# Sheet1.net
KiCad netlist of a schematic drawn in Altium Designer
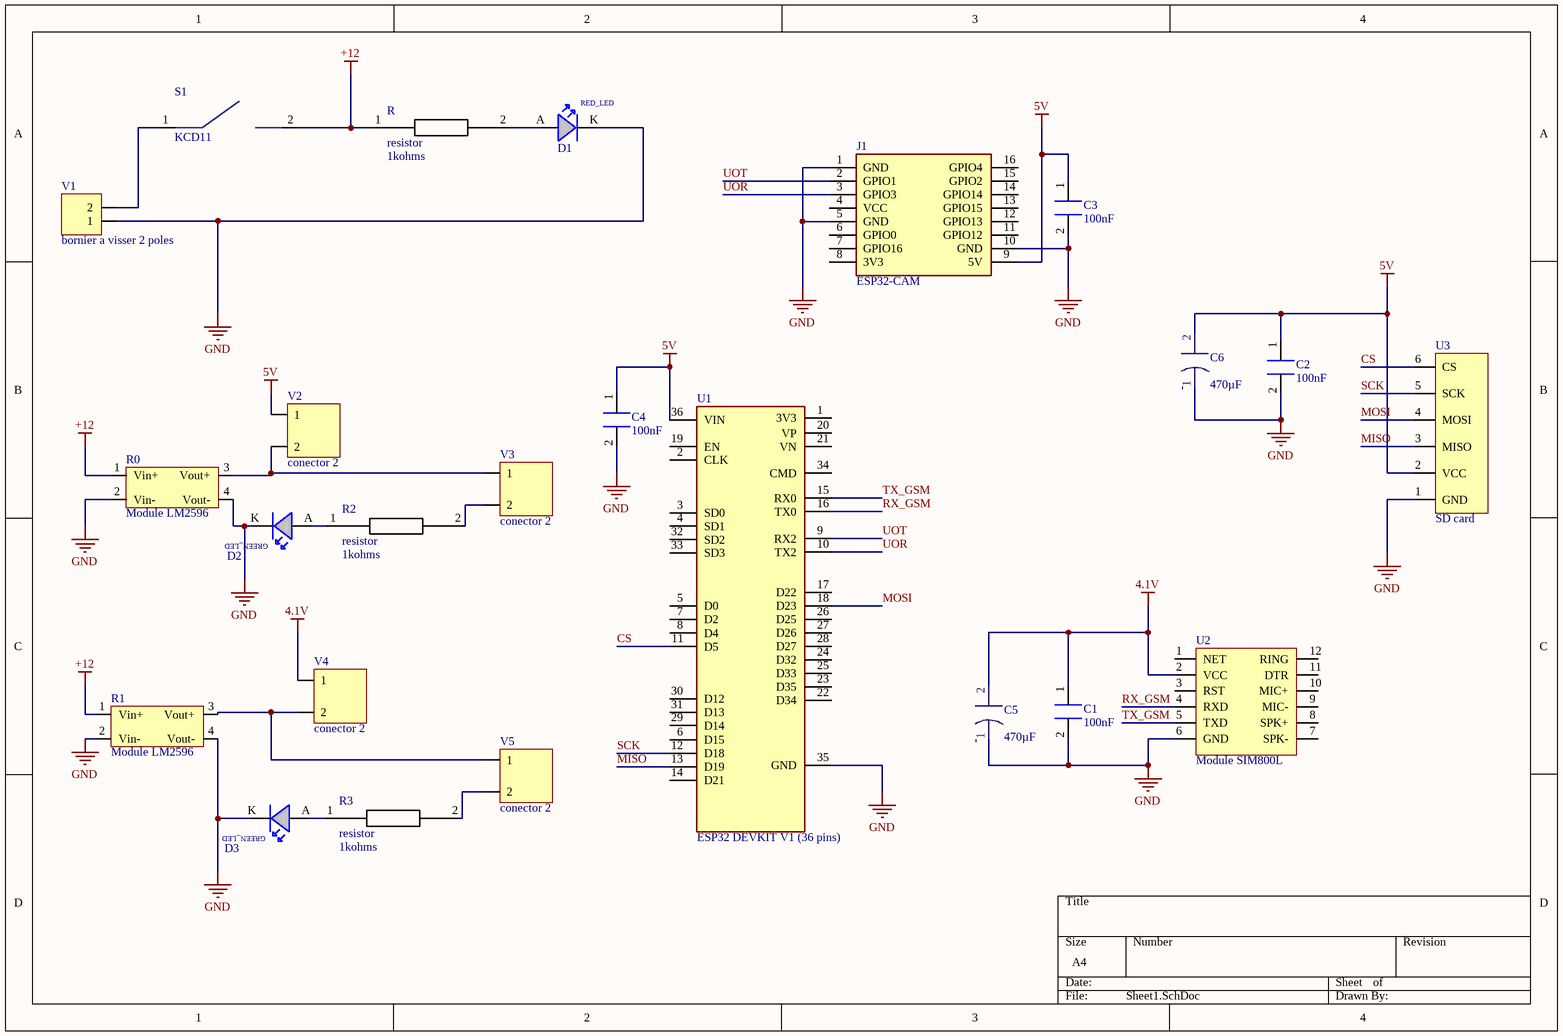
[diagram p0: Sheet1.SchDoc]

(export (version "E")
  (design (tool "Eeschema 10.0.6"))
  (components
    (comp (ref "C1")
      (value "capacitor")
      (footprint "CAPACITOR")
      (fields (field (name "CAP EN UF OU NF") "100nF"))
      (libsource (lib "Devices") (part "capacitor"))
    )
    (comp (ref "C2")
      (value "capacitor")
      (footprint "CAPACITOR")
      (fields (field (name "CAP EN UF OU NF") "100nF"))
      (libsource (lib "Devices") (part "capacitor"))
    )
    (comp (ref "C3")
      (value "capacitor")
      (footprint "CAPACITOR")
      (fields (field (name "CAP EN UF OU NF") "100nF"))
      (libsource (lib "Devices") (part "capacitor"))
    )
    (comp (ref "C4")
      (value "capacitor")
      (footprint "CAPACITOR")
      (fields (field (name "CAP EN UF OU NF") "100nF"))
      (libsource (lib "Devices") (part "capacitor"))
    )
    (comp (ref "C5")
      (value "470µF")
      (footprint "condensateur chimique 470f 16v -")
      (fields (field (name "Comment") "condensateur chimique_470uF"))
      (libsource (lib "condensateur") (part "condensateur chimique_470uF"))
    )
    (comp (ref "C6")
      (value "470µF")
      (footprint "condensateur chimique 470f 16v -")
      (fields (field (name "Comment") "condensateur chimique_470uF"))
      (libsource (lib "condensateur") (part "condensateur chimique_470uF"))
    )
    (comp (ref "D1") (value "LED_RED") (footprint "LED") (libsource (lib "Devices") (part "LED_RED")))
    (comp (ref "D2")
      (value "LED_GREEN")
      (footprint "LED_GREEN")
      (libsource (lib "Devices") (part "LED_GREEN"))
    )
    (comp (ref "D3")
      (value "LED_GREEN")
      (footprint "LED_GREEN")
      (libsource (lib "Devices") (part "LED_GREEN"))
    )
    (comp (ref "J1")
      (value "ESP32-CAM")
      (footprint "ESP32-CAM")
      (fields (field (name "MF") "AI-Thinker"))
      (libsource (lib "esp32") (part "ESP32-CAM"))
    )
    (comp (ref "R")
      (value "resistor")
      (footprint "RESISTOR")
      (fields (field (name "R") "1kohms"))
      (libsource (lib "resistor") (part "resistor"))
    )
    (comp (ref "R0")
      (value "Module LM2596")
      (footprint "Module LM2596")
      (libsource (lib "Alimentation Réglable") (part "Module LM2596"))
    )
    (comp (ref "R1")
      (value "Module LM2596")
      (footprint "Module LM2596")
      (libsource (lib "Alimentation Réglable") (part "Module LM2596"))
    )
    (comp (ref "R2")
      (value "resistor")
      (footprint "RESISTOR")
      (fields (field (name "R") "1kohms"))
      (libsource (lib "resistor") (part "resistor"))
    )
    (comp (ref "R3")
      (value "resistor")
      (footprint "RESISTOR")
      (fields (field (name "R") "1kohms"))
      (libsource (lib "resistor") (part "resistor"))
    )
    (comp (ref "S1") (value "KCD11") (footprint "PCBComponent_1") (libsource (lib "switch") (part "KCD11")))
    (comp (ref "U1")
      (value "ESP32 DEVKIT V1 (36 pins)")
      (footprint "ESP32 DEVKIT V1 (36 pins)")
      (fields (field (name "MF") "Do it") (field (name "MP") "ESP32-DEVKIT-V1"))
      (libsource (lib "esp32") (part "ESP32 DEVKIT V1 (36 pins)"))
    )
    (comp (ref "U2")
      (value "Module SIM800L")
      (footprint "SIM800L")
      (libsource (lib "SIM800L") (part "SIM800L"))
    )
    (comp (ref "U3")
      (value "SD card")
      (footprint "SULLINS_PPTC061LFBN-RC - duplicate")
      (libsource (lib "SD card") (part "SD card V2"))
    )
    (comp (ref "V1")
      (value "bornier a visser 2 poles")
      (footprint "bornier a visser 2 poles")
      (libsource (lib "bornier") (part "bornier a visser 2 poles"))
    )
    (comp (ref "V2")
      (value "conector 2")
      (footprint "PCBComponent_1")
      (libsource (lib "connector devives") (part "conector 2"))
    )
    (comp (ref "V3")
      (value "conector 2")
      (footprint "PCBComponent_1")
      (libsource (lib "connector devives") (part "conector 2"))
    )
    (comp (ref "V4")
      (value "conector 2")
      (footprint "PCBComponent_1")
      (libsource (lib "connector devives") (part "conector 2"))
    )
    (comp (ref "V5")
      (value "conector 2")
      (footprint "PCBComponent_1")
      (libsource (lib "connector devives") (part "conector 2"))
    )
  )
  (nets
    (net (code "1") (name "+12") (class "Default")
      (node (ref "R") (pin "1") (pinfunction "1_1") (pintype "passive"))
      (node (ref "R0") (pin "1") (pinfunction "Vin+_1") (pintype "passive"))
      (node (ref "R1") (pin "1") (pinfunction "Vin+_1") (pintype "passive"))
      (node (ref "S1") (pin "2") (pinfunction "2_2") (pintype "passive"))
    )
    (net (code "2") (name "/CS") (class "Default")
      (node (ref "U1") (pin "11") (pinfunction "D5_11") (pintype "passive"))
      (node (ref "U3") (pin "6") (pinfunction "CS_6") (pintype "passive"))
    )
    (net (code "3") (name "/MISO") (class "Default")
      (node (ref "U1") (pin "13") (pinfunction "D19_13") (pintype "passive"))
      (node (ref "U3") (pin "3") (pinfunction "MISO_3") (pintype "passive"))
    )
    (net (code "4") (name "/MOSI") (class "Default")
      (node (ref "U1") (pin "18") (pinfunction "D23_18") (pintype "passive"))
      (node (ref "U3") (pin "4") (pinfunction "MOSI_4") (pintype "passive"))
    )
    (net (code "5") (name "/RX_GSM") (class "Default")
      (node (ref "U1") (pin "16") (pinfunction "TX0_16") (pintype "passive"))
      (node (ref "U2") (pin "4") (pinfunction "RXD_4") (pintype "passive"))
    )
    (net (code "6") (name "/SCK") (class "Default")
      (node (ref "U1") (pin "12") (pinfunction "D18_12") (pintype "passive"))
      (node (ref "U3") (pin "5") (pinfunction "SCK_5") (pintype "passive"))
    )
    (net (code "7") (name "/TX_GSM") (class "Default")
      (node (ref "U1") (pin "15") (pinfunction "RX0_15") (pintype "passive"))
      (node (ref "U2") (pin "5") (pinfunction "TXD_5") (pintype "passive"))
    )
    (net (code "8") (name "/UOR") (class "Default")
      (node (ref "J1") (pin "3") (pinfunction "GPIO3_3") (pintype "passive"))
      (node (ref "U1") (pin "10") (pinfunction "TX2_10") (pintype "passive"))
    )
    (net (code "9") (name "/UOT") (class "Default")
      (node (ref "J1") (pin "2") (pinfunction "GPIO1_2") (pintype "passive"))
      (node (ref "U1") (pin "9") (pinfunction "RX2_9") (pintype "passive"))
    )
    (net (code "10") (name "4.1V") (class "Default")
      (node (ref "C1") (pin "1") (pinfunction "1_1") (pintype "passive"))
      (node (ref "C5") (pin "2") (pinfunction "2_2") (pintype "passive"))
      (node (ref "U2") (pin "2") (pinfunction "VCC_2") (pintype "passive"))
      (node (ref "V4") (pin "1") (pinfunction "1_1") (pintype "passive"))
    )
    (net (code "11") (name "5V") (class "Default")
      (node (ref "C2") (pin "1") (pinfunction "1_1") (pintype "passive"))
      (node (ref "C3") (pin "1") (pinfunction "1_1") (pintype "passive"))
      (node (ref "C4") (pin "1") (pinfunction "1_1") (pintype "passive"))
      (node (ref "C6") (pin "2") (pinfunction "2_2") (pintype "passive"))
      (node (ref "J1") (pin "9") (pinfunction "5V_9") (pintype "passive"))
      (node (ref "U1") (pin "36") (pinfunction "VIN_36") (pintype "passive"))
      (node (ref "U3") (pin "2") (pinfunction "VCC_2") (pintype "passive"))
      (node (ref "V2") (pin "1") (pinfunction "1_1") (pintype "passive"))
    )
    (net (code "12") (name "GND") (class "Default")
      (node (ref "C1") (pin "2") (pinfunction "2_2") (pintype "passive"))
      (node (ref "C2") (pin "2") (pinfunction "2_2") (pintype "passive"))
      (node (ref "C3") (pin "2") (pinfunction "2_2") (pintype "passive"))
      (node (ref "C4") (pin "2") (pinfunction "2_2") (pintype "passive"))
      (node (ref "C5") (pin "1") (pinfunction "1_1") (pintype "passive"))
      (node (ref "C6") (pin "1") (pinfunction "1_1") (pintype "passive"))
      (node (ref "D1") (pin "K") (pintype "passive"))
      (node (ref "D2") (pin "K") (pintype "passive"))
      (node (ref "D3") (pin "K") (pintype "passive"))
      (node (ref "J1") (pin "1") (pinfunction "GND_1") (pintype "passive"))
      (node (ref "J1") (pin "10") (pinfunction "GND_10") (pintype "passive"))
      (node (ref "J1") (pin "5") (pinfunction "GND_5") (pintype "passive"))
      (node (ref "R0") (pin "2") (pinfunction "Vin-_2") (pintype "passive"))
      (node (ref "R0") (pin "4") (pinfunction "Vout-_4") (pintype "passive"))
      (node (ref "R1") (pin "2") (pinfunction "Vin-_2") (pintype "passive"))
      (node (ref "R1") (pin "4") (pinfunction "Vout-_4") (pintype "passive"))
      (node (ref "U1") (pin "35") (pinfunction "GND_35") (pintype "passive"))
      (node (ref "U2") (pin "6") (pinfunction "GND_6") (pintype "passive"))
      (node (ref "U3") (pin "1") (pinfunction "GND_1") (pintype "passive"))
      (node (ref "V1") (pin "1") (pinfunction "1_1") (pintype "passive"))
    )
    (net (code "13") (name "Net-(D1-PadA)") (class "Default")
      (node (ref "D1") (pin "A") (pintype "passive"))
      (node (ref "R") (pin "2") (pinfunction "2_2") (pintype "passive"))
    )
    (net (code "14") (name "Net-(D2-PadA)") (class "Default")
      (node (ref "D2") (pin "A") (pintype "passive"))
      (node (ref "R2") (pin "1") (pinfunction "1_1") (pintype "passive"))
    )
    (net (code "15") (name "Net-(D3-PadA)") (class "Default")
      (node (ref "D3") (pin "A") (pintype "passive"))
      (node (ref "R3") (pin "1") (pinfunction "1_1") (pintype "passive"))
    )
    (net (code "16") (name "Net-(R0-Vout+)") (class "Default")
      (node (ref "R0") (pin "3") (pinfunction "Vout+_3") (pintype "passive"))
      (node (ref "V2") (pin "2") (pinfunction "2_2") (pintype "passive"))
      (node (ref "V3") (pin "1") (pinfunction "1_1") (pintype "passive"))
    )
    (net (code "17") (name "Net-(R1-Vout+)") (class "Default")
      (node (ref "R1") (pin "3") (pinfunction "Vout+_3") (pintype "passive"))
      (node (ref "V4") (pin "2") (pinfunction "2_2") (pintype "passive"))
      (node (ref "V5") (pin "1") (pinfunction "1_1") (pintype "passive"))
    )
    (net (code "18") (name "Net-(R2-Pad2)") (class "Default")
      (node (ref "R2") (pin "2") (pinfunction "2_2") (pintype "passive"))
      (node (ref "V3") (pin "2") (pinfunction "2_2") (pintype "passive"))
    )
    (net (code "19") (name "Net-(R3-Pad2)") (class "Default")
      (node (ref "R3") (pin "2") (pinfunction "2_2") (pintype "passive"))
      (node (ref "V5") (pin "2") (pinfunction "2_2") (pintype "passive"))
    )
    (net (code "20") (name "Net-(S1-Pad1)") (class "Default")
      (node (ref "S1") (pin "1") (pinfunction "1_1") (pintype "passive"))
      (node (ref "V1") (pin "2") (pinfunction "2_2") (pintype "passive"))
    )
    (net (code "21") (name "unconnected-(J1-3V3-Pad8)") (class "Default")
      (node (ref "J1") (pin "8") (pinfunction "3V3_8") (pintype "passive"))
    )
    (net (code "22") (name "unconnected-(J1-GPIO0-Pad6)") (class "Default")
      (node (ref "J1") (pin "6") (pinfunction "GPIO0_6") (pintype "passive"))
    )
    (net (code "23") (name "unconnected-(J1-GPIO2-Pad15)") (class "Default")
      (node (ref "J1") (pin "15") (pinfunction "GPIO2_15") (pintype "passive"))
    )
    (net (code "24") (name "unconnected-(J1-GPIO4-Pad16)") (class "Default")
      (node (ref "J1") (pin "16") (pinfunction "GPIO4_16") (pintype "passive"))
    )
    (net (code "25") (name "unconnected-(J1-GPIO12-Pad11)") (class "Default")
      (node (ref "J1") (pin "11") (pinfunction "GPIO12_11") (pintype "passive"))
    )
    (net (code "26") (name "unconnected-(J1-GPIO13-Pad12)") (class "Default")
      (node (ref "J1") (pin "12") (pinfunction "GPIO13_12") (pintype "passive"))
    )
    (net (code "27") (name "unconnected-(J1-GPIO14-Pad14)") (class "Default")
      (node (ref "J1") (pin "14") (pinfunction "GPIO14_14") (pintype "passive"))
    )
    (net (code "28") (name "unconnected-(J1-GPIO15-Pad13)") (class "Default")
      (node (ref "J1") (pin "13") (pinfunction "GPIO15_13") (pintype "passive"))
    )
    (net (code "29") (name "unconnected-(J1-GPIO16-Pad7)") (class "Default")
      (node (ref "J1") (pin "7") (pinfunction "GPIO16_7") (pintype "passive"))
    )
    (net (code "30") (name "unconnected-(J1-VCC-Pad4)") (class "Default")
      (node (ref "J1") (pin "4") (pinfunction "VCC_4") (pintype "passive"))
    )
    (net (code "31") (name "unconnected-(U1-3V3-Pad1)") (class "Default")
      (node (ref "U1") (pin "1") (pinfunction "3V3_1") (pintype "passive"))
    )
    (net (code "32") (name "unconnected-(U1-CLK-Pad2)") (class "Default")
      (node (ref "U1") (pin "2") (pinfunction "CLK_2") (pintype "passive"))
    )
    (net (code "33") (name "unconnected-(U1-CMD-Pad34)") (class "Default")
      (node (ref "U1") (pin "34") (pinfunction "CMD_34") (pintype "passive"))
    )
    (net (code "34") (name "unconnected-(U1-D0-Pad5)") (class "Default")
      (node (ref "U1") (pin "5") (pinfunction "D0_5") (pintype "passive"))
    )
    (net (code "35") (name "unconnected-(U1-D2-Pad7)") (class "Default")
      (node (ref "U1") (pin "7") (pinfunction "D2_7") (pintype "passive"))
    )
    (net (code "36") (name "unconnected-(U1-D4-Pad8)") (class "Default")
      (node (ref "U1") (pin "8") (pinfunction "D4_8") (pintype "passive"))
    )
    (net (code "37") (name "unconnected-(U1-D12-Pad30)") (class "Default")
      (node (ref "U1") (pin "30") (pinfunction "D12_30") (pintype "passive"))
    )
    (net (code "38") (name "unconnected-(U1-D13-Pad31)") (class "Default")
      (node (ref "U1") (pin "31") (pinfunction "D13_31") (pintype "passive"))
    )
    (net (code "39") (name "unconnected-(U1-D14-Pad29)") (class "Default")
      (node (ref "U1") (pin "29") (pinfunction "D14_29") (pintype "passive"))
    )
    (net (code "40") (name "unconnected-(U1-D15-Pad6)") (class "Default")
      (node (ref "U1") (pin "6") (pinfunction "D15_6") (pintype "passive"))
    )
    (net (code "41") (name "unconnected-(U1-D21-Pad14)") (class "Default")
      (node (ref "U1") (pin "14") (pinfunction "D21_14") (pintype "passive"))
    )
    (net (code "42") (name "unconnected-(U1-D22-Pad17)") (class "Default")
      (node (ref "U1") (pin "17") (pinfunction "D22_17") (pintype "passive"))
    )
    (net (code "43") (name "unconnected-(U1-D25-Pad26)") (class "Default")
      (node (ref "U1") (pin "26") (pinfunction "D25_26") (pintype "passive"))
    )
    (net (code "44") (name "unconnected-(U1-D26-Pad27)") (class "Default")
      (node (ref "U1") (pin "27") (pinfunction "D26_27") (pintype "passive"))
    )
    (net (code "45") (name "unconnected-(U1-D27-Pad28)") (class "Default")
      (node (ref "U1") (pin "28") (pinfunction "D27_28") (pintype "passive"))
    )
    (net (code "46") (name "unconnected-(U1-D32-Pad24)") (class "Default")
      (node (ref "U1") (pin "24") (pinfunction "D32_24") (pintype "passive"))
    )
    (net (code "47") (name "unconnected-(U1-D33-Pad25)") (class "Default")
      (node (ref "U1") (pin "25") (pinfunction "D33_25") (pintype "passive"))
    )
    (net (code "48") (name "unconnected-(U1-D34-Pad22)") (class "Default")
      (node (ref "U1") (pin "22") (pinfunction "D34_22") (pintype "passive"))
    )
    (net (code "49") (name "unconnected-(U1-D35-Pad23)") (class "Default")
      (node (ref "U1") (pin "23") (pinfunction "D35_23") (pintype "passive"))
    )
    (net (code "50") (name "unconnected-(U1-EN-Pad19)") (class "Default")
      (node (ref "U1") (pin "19") (pinfunction "EN_19") (pintype "passive"))
    )
    (net (code "51") (name "unconnected-(U1-SD0-Pad3)") (class "Default")
      (node (ref "U1") (pin "3") (pinfunction "SD0_3") (pintype "passive"))
    )
    (net (code "52") (name "unconnected-(U1-SD1-Pad4)") (class "Default")
      (node (ref "U1") (pin "4") (pinfunction "SD1_4") (pintype "passive"))
    )
    (net (code "53") (name "unconnected-(U1-SD2-Pad32)") (class "Default")
      (node (ref "U1") (pin "32") (pinfunction "SD2_32") (pintype "passive"))
    )
    (net (code "54") (name "unconnected-(U1-SD3-Pad33)") (class "Default")
      (node (ref "U1") (pin "33") (pinfunction "SD3_33") (pintype "passive"))
    )
    (net (code "55") (name "unconnected-(U1-VN-Pad21)") (class "Default")
      (node (ref "U1") (pin "21") (pinfunction "VN_21") (pintype "passive"))
    )
    (net (code "56") (name "unconnected-(U1-VP-Pad20)") (class "Default")
      (node (ref "U1") (pin "20") (pinfunction "VP_20") (pintype "passive"))
    )
    (net (code "57") (name "unconnected-(U2-DTR-Pad11)") (class "Default")
      (node (ref "U2") (pin "11") (pinfunction "DTR_11") (pintype "passive"))
    )
    (net (code "58") (name "unconnected-(U2-MIC+-Pad10)") (class "Default")
      (node (ref "U2") (pin "10") (pinfunction "MIC+_10") (pintype "passive"))
    )
    (net (code "59") (name "unconnected-(U2-MIC--Pad9)") (class "Default")
      (node (ref "U2") (pin "9") (pinfunction "MIC-_9") (pintype "passive"))
    )
    (net (code "60") (name "unconnected-(U2-NET-Pad1)") (class "Default")
      (node (ref "U2") (pin "1") (pinfunction "NET_1") (pintype "passive"))
    )
    (net (code "61") (name "unconnected-(U2-RING-Pad12)") (class "Default")
      (node (ref "U2") (pin "12") (pinfunction "RING_12") (pintype "passive"))
    )
    (net (code "62") (name "unconnected-(U2-RST-Pad3)") (class "Default")
      (node (ref "U2") (pin "3") (pinfunction "RST_3") (pintype "passive"))
    )
    (net (code "63") (name "unconnected-(U2-SPK+-Pad8)") (class "Default")
      (node (ref "U2") (pin "8") (pinfunction "SPK+_8") (pintype "passive"))
    )
    (net (code "64") (name "unconnected-(U2-SPK--Pad7)") (class "Default")
      (node (ref "U2") (pin "7") (pinfunction "SPK-_7") (pintype "passive"))
    )
  )
)
